# tdt_rereference.net
KiCad netlist of a schematic drawn in EAGLE
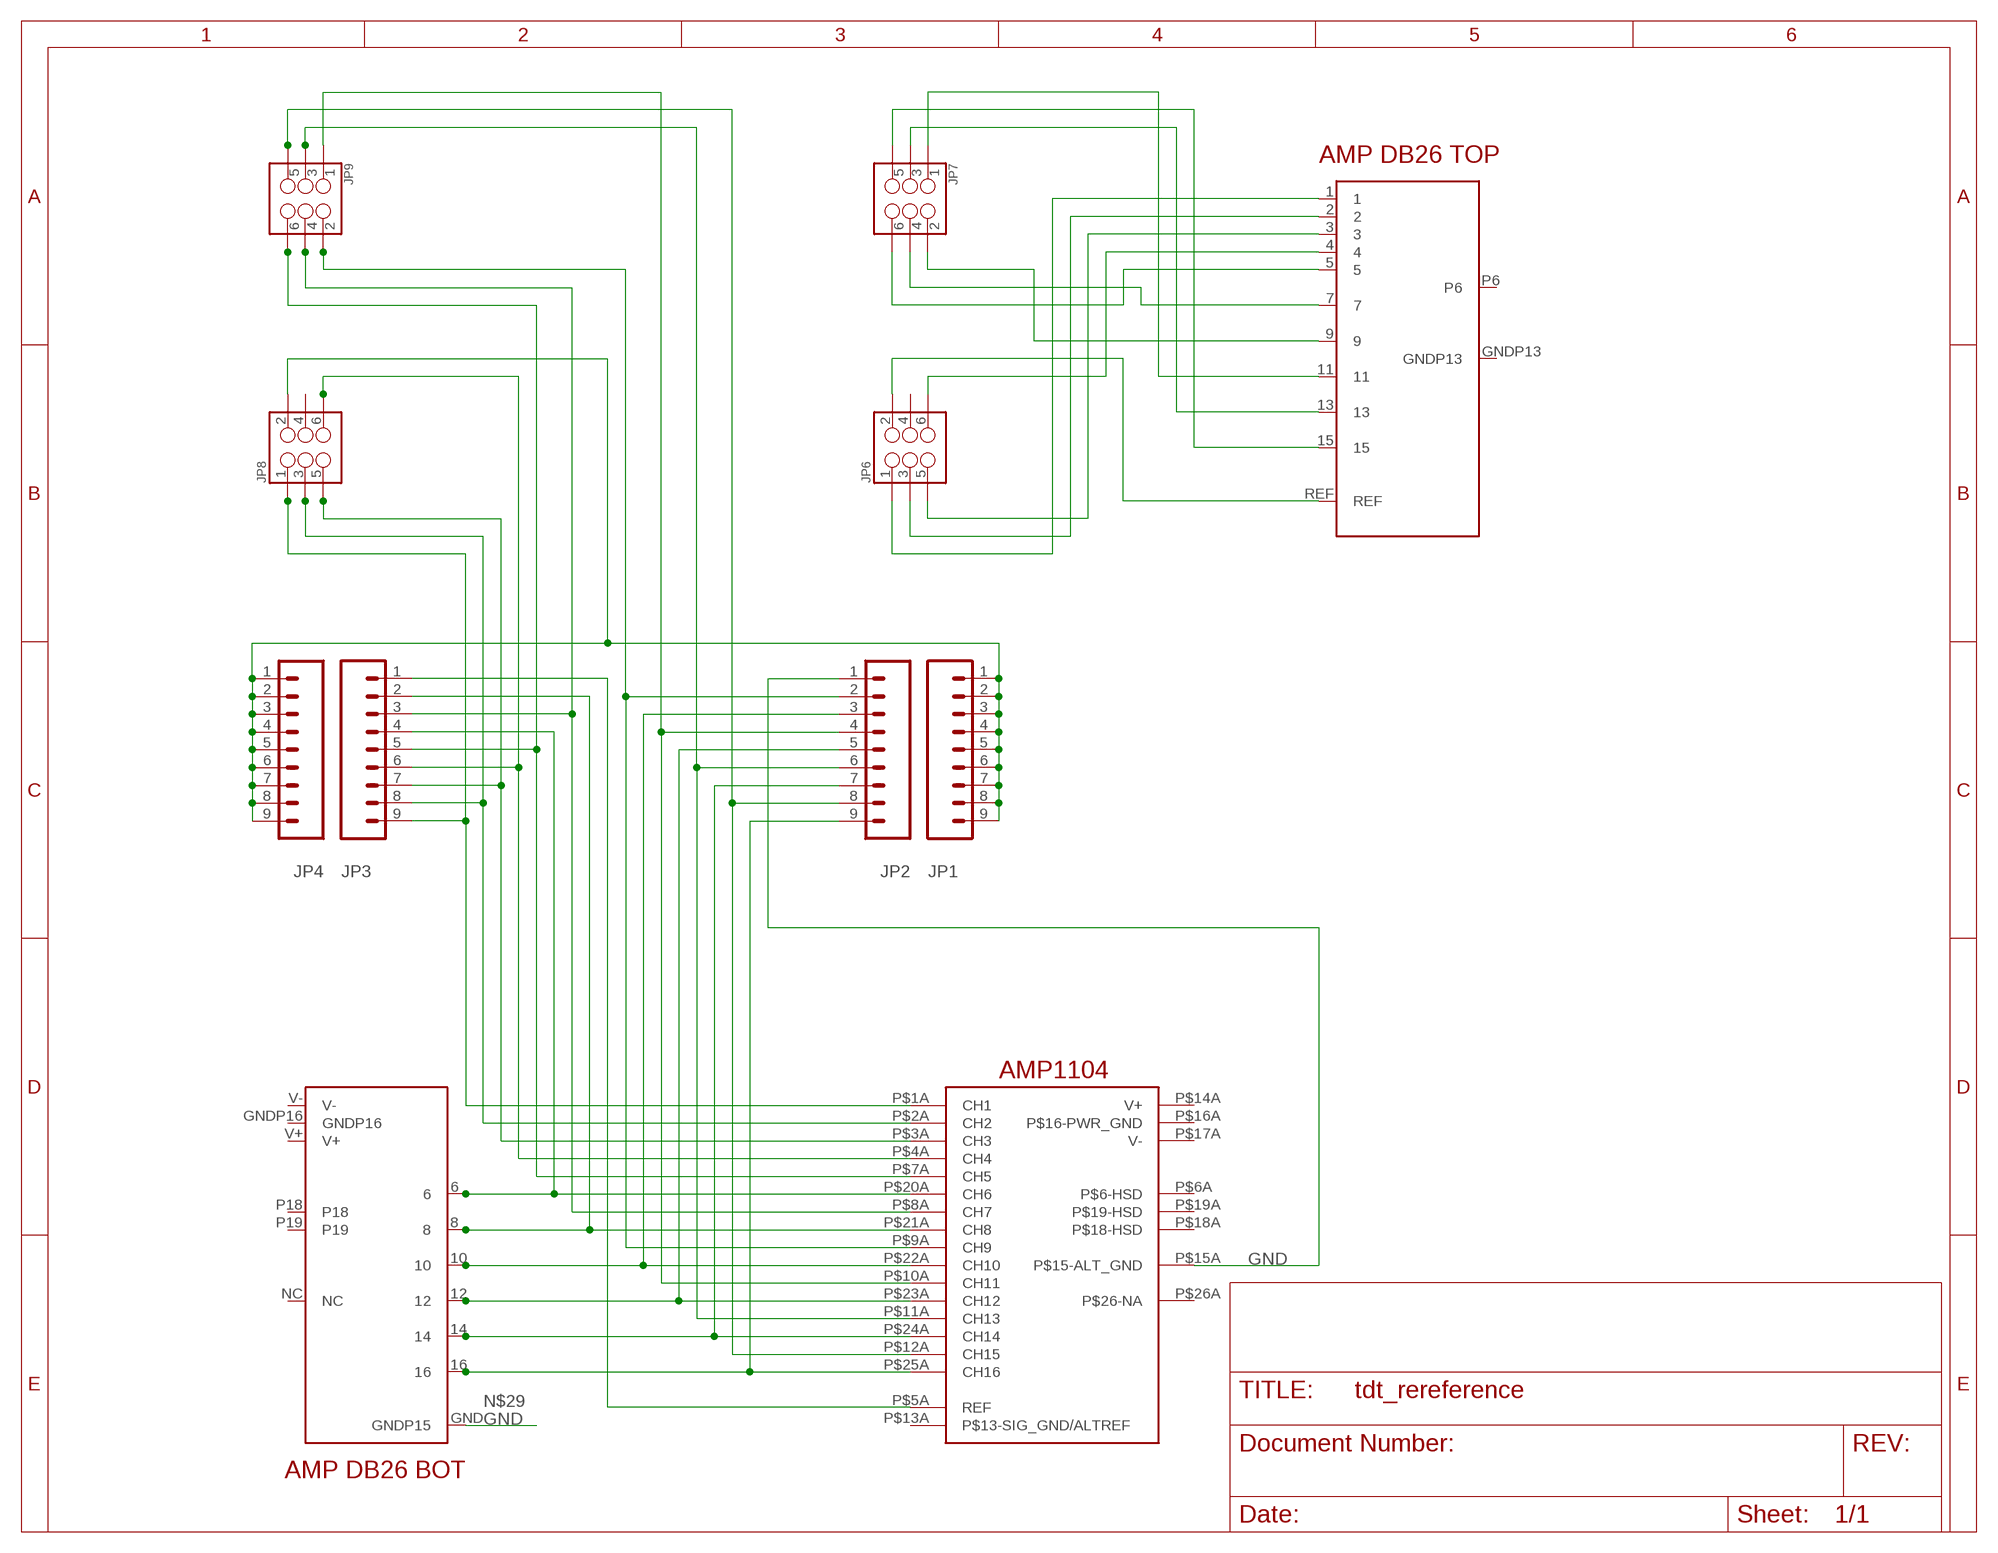
[diagram p0: schematic, sheet 1]

(export (version "E")
  (design (tool "Eeschema 10.0.6"))
  (components
    (comp (ref "JP1")
      (value "M09")
      (footprint "eagle-import:1X09")
      (libsource (lib "eagle-import") (part "M09"))
    )
    (comp (ref "JP2")
      (value "M09")
      (footprint "eagle-import:1X09")
      (libsource (lib "eagle-import") (part "M09"))
    )
    (comp (ref "JP3")
      (value "M09")
      (footprint "eagle-import:1X09")
      (libsource (lib "eagle-import") (part "M09"))
    )
    (comp (ref "JP4")
      (value "M09")
      (footprint "eagle-import:1X09")
      (libsource (lib "eagle-import") (part "M09"))
    )
    (comp (ref "JP6")
      (value "M03X22X3_SILK_MALE_PTH")
      (footprint "eagle-import:2X3")
      (libsource (lib "eagle-import") (part "M03X22X3_SILK_MALE_PTH"))
    )
    (comp (ref "JP7")
      (value "M03X22X3_SILK_MALE_PTH")
      (footprint "eagle-import:2X3")
      (libsource (lib "eagle-import") (part "M03X22X3_SILK_MALE_PTH"))
    )
    (comp (ref "JP8")
      (value "M03X22X3_SILK_MALE_PTH")
      (footprint "eagle-import:2X3")
      (libsource (lib "eagle-import") (part "M03X22X3_SILK_MALE_PTH"))
    )
    (comp (ref "JP9")
      (value "M03X22X3_SILK_MALE_PTH")
      (footprint "eagle-import:2X3")
      (libsource (lib "eagle-import") (part "M03X22X3_SILK_MALE_PTH"))
    )
    (comp (ref "U$1")
      (value "DB26-MALE-BOT")
      (footprint "eagle-import:DB26-MALE-BOT")
      (libsource (lib "eagle-import") (part "DB26-MALE-BOT"))
    )
    (comp (ref "U$2")
      (value "DB26-MALE-TOP")
      (footprint "eagle-import:DB26-MALE-TOP")
      (libsource (lib "eagle-import") (part "DB26-MALE-TOP"))
    )
    (comp (ref "U$3")
      (value "AMP1104")
      (footprint "eagle-import:AMP1104")
      (libsource (lib "eagle-import") (part "AMP1104"))
    )
  )
  (nets
    (net (code "1") (name "/GND") (class "Default")
      (node (ref "JP2") (pin "1") (pinfunction "1_1") (pintype "passive"))
      (node (ref "U$1") (pin "GND") (pinfunction "GNDP15_GND") (pintype "bidirectional"))
      (node (ref "U$3") (pin "P$15A") (pinfunction "P$15-ALT_GND_P$15A") (pintype "bidirectional"))
    )
    (net (code "2") (name "/N$29") (class "Default")
      (node (ref "JP3") (pin "1") (pinfunction "1_1") (pintype "passive"))
      (node (ref "U$3") (pin "P$5A") (pinfunction "REF_P$5A") (pintype "bidirectional"))
    )
    (net (code "3") (name "Net-(JP1-Pad1)") (class "Default")
      (node (ref "JP1") (pin "1") (pinfunction "1_1") (pintype "passive"))
      (node (ref "JP1") (pin "2") (pinfunction "2_2") (pintype "passive"))
      (node (ref "JP1") (pin "3") (pinfunction "3_3") (pintype "passive"))
      (node (ref "JP1") (pin "4") (pinfunction "4_4") (pintype "passive"))
      (node (ref "JP1") (pin "5") (pinfunction "5_5") (pintype "passive"))
      (node (ref "JP1") (pin "6") (pinfunction "6_6") (pintype "passive"))
      (node (ref "JP1") (pin "7") (pinfunction "7_7") (pintype "passive"))
      (node (ref "JP1") (pin "8") (pinfunction "8_8") (pintype "passive"))
      (node (ref "JP1") (pin "9") (pinfunction "9_9") (pintype "passive"))
      (node (ref "JP4") (pin "1") (pinfunction "1_1") (pintype "passive"))
      (node (ref "JP4") (pin "2") (pinfunction "2_2") (pintype "passive"))
      (node (ref "JP4") (pin "3") (pinfunction "3_3") (pintype "passive"))
      (node (ref "JP4") (pin "4") (pinfunction "4_4") (pintype "passive"))
      (node (ref "JP4") (pin "5") (pinfunction "5_5") (pintype "passive"))
      (node (ref "JP4") (pin "6") (pinfunction "6_6") (pintype "passive"))
      (node (ref "JP4") (pin "7") (pinfunction "7_7") (pintype "passive"))
      (node (ref "JP4") (pin "8") (pinfunction "8_8") (pintype "passive"))
      (node (ref "JP4") (pin "9") (pinfunction "9_9") (pintype "passive"))
      (node (ref "JP8") (pin "2") (pinfunction "2_2") (pintype "bidirectional"))
    )
    (net (code "4") (name "Net-(JP6-Pad1)") (class "Default")
      (node (ref "JP6") (pin "1") (pinfunction "1_1") (pintype "bidirectional"))
      (node (ref "U$2") (pin "1") (pinfunction "1_1") (pintype "bidirectional"))
    )
    (net (code "5") (name "Net-(JP6-Pad2)") (class "Default")
      (node (ref "JP6") (pin "2") (pinfunction "2_2") (pintype "bidirectional"))
      (node (ref "U$2") (pin "REF") (pinfunction "REF_REF") (pintype "bidirectional"))
    )
    (net (code "6") (name "Net-(JP6-Pad3)") (class "Default")
      (node (ref "JP6") (pin "3") (pinfunction "3_3") (pintype "bidirectional"))
      (node (ref "U$2") (pin "2") (pinfunction "2_2") (pintype "bidirectional"))
    )
    (net (code "7") (name "Net-(JP6-Pad5)") (class "Default")
      (node (ref "JP6") (pin "5") (pinfunction "5_5") (pintype "bidirectional"))
      (node (ref "U$2") (pin "3") (pinfunction "3_3") (pintype "bidirectional"))
    )
    (net (code "8") (name "Net-(JP6-Pad6)") (class "Default")
      (node (ref "JP6") (pin "6") (pinfunction "6_6") (pintype "bidirectional"))
      (node (ref "U$2") (pin "4") (pinfunction "4_4") (pintype "bidirectional"))
    )
    (net (code "9") (name "Net-(JP7-Pad1)") (class "Default")
      (node (ref "JP7") (pin "1") (pinfunction "1_1") (pintype "bidirectional"))
      (node (ref "U$2") (pin "11") (pinfunction "11_11") (pintype "bidirectional"))
    )
    (net (code "10") (name "Net-(JP7-Pad2)") (class "Default")
      (node (ref "JP7") (pin "2") (pinfunction "2_2") (pintype "bidirectional"))
      (node (ref "U$2") (pin "9") (pinfunction "9_9") (pintype "bidirectional"))
    )
    (net (code "11") (name "Net-(JP7-Pad3)") (class "Default")
      (node (ref "JP7") (pin "3") (pinfunction "3_3") (pintype "bidirectional"))
      (node (ref "U$2") (pin "13") (pinfunction "13_13") (pintype "bidirectional"))
    )
    (net (code "12") (name "Net-(JP7-Pad4)") (class "Default")
      (node (ref "JP7") (pin "4") (pinfunction "4_4") (pintype "bidirectional"))
      (node (ref "U$2") (pin "7") (pinfunction "7_7") (pintype "bidirectional"))
    )
    (net (code "13") (name "Net-(JP7-Pad5)") (class "Default")
      (node (ref "JP7") (pin "5") (pinfunction "5_5") (pintype "bidirectional"))
      (node (ref "U$2") (pin "15") (pinfunction "15_15") (pintype "bidirectional"))
    )
    (net (code "14") (name "Net-(JP7-Pad6)") (class "Default")
      (node (ref "JP7") (pin "6") (pinfunction "6_6") (pintype "bidirectional"))
      (node (ref "U$2") (pin "5") (pinfunction "5_5") (pintype "bidirectional"))
    )
    (net (code "15") (name "Net-(U$3-CH1)") (class "Default")
      (node (ref "JP3") (pin "9") (pinfunction "9_9") (pintype "passive"))
      (node (ref "JP8") (pin "1") (pinfunction "1_1") (pintype "bidirectional"))
      (node (ref "U$3") (pin "P$1A") (pinfunction "CH1_P$1A") (pintype "bidirectional"))
    )
    (net (code "16") (name "Net-(U$3-CH2)") (class "Default")
      (node (ref "JP3") (pin "8") (pinfunction "8_8") (pintype "passive"))
      (node (ref "JP8") (pin "3") (pinfunction "3_3") (pintype "bidirectional"))
      (node (ref "U$3") (pin "P$2A") (pinfunction "CH2_P$2A") (pintype "bidirectional"))
    )
    (net (code "17") (name "Net-(U$3-CH3)") (class "Default")
      (node (ref "JP3") (pin "7") (pinfunction "7_7") (pintype "passive"))
      (node (ref "JP8") (pin "5") (pinfunction "5_5") (pintype "bidirectional"))
      (node (ref "U$3") (pin "P$3A") (pinfunction "CH3_P$3A") (pintype "bidirectional"))
    )
    (net (code "18") (name "Net-(U$3-CH4)") (class "Default")
      (node (ref "JP3") (pin "6") (pinfunction "6_6") (pintype "passive"))
      (node (ref "JP8") (pin "6") (pinfunction "6_6") (pintype "bidirectional"))
      (node (ref "U$3") (pin "P$4A") (pinfunction "CH4_P$4A") (pintype "bidirectional"))
    )
    (net (code "19") (name "Net-(U$3-CH5)") (class "Default")
      (node (ref "JP3") (pin "5") (pinfunction "5_5") (pintype "passive"))
      (node (ref "JP9") (pin "6") (pinfunction "6_6") (pintype "bidirectional"))
      (node (ref "U$3") (pin "P$7A") (pinfunction "CH5_P$7A") (pintype "bidirectional"))
    )
    (net (code "20") (name "Net-(U$3-CH6)") (class "Default")
      (node (ref "JP3") (pin "4") (pinfunction "4_4") (pintype "passive"))
      (node (ref "U$1") (pin "6") (pinfunction "6_6") (pintype "bidirectional"))
      (node (ref "U$3") (pin "P$20A") (pinfunction "CH6_P$20A") (pintype "bidirectional"))
    )
    (net (code "21") (name "Net-(U$3-CH7)") (class "Default")
      (node (ref "JP3") (pin "3") (pinfunction "3_3") (pintype "passive"))
      (node (ref "JP9") (pin "4") (pinfunction "4_4") (pintype "bidirectional"))
      (node (ref "U$3") (pin "P$8A") (pinfunction "CH7_P$8A") (pintype "bidirectional"))
    )
    (net (code "22") (name "Net-(U$3-CH8)") (class "Default")
      (node (ref "JP3") (pin "2") (pinfunction "2_2") (pintype "passive"))
      (node (ref "U$1") (pin "8") (pinfunction "8_8") (pintype "bidirectional"))
      (node (ref "U$3") (pin "P$21A") (pinfunction "CH8_P$21A") (pintype "bidirectional"))
    )
    (net (code "23") (name "Net-(U$3-CH9)") (class "Default")
      (node (ref "JP2") (pin "2") (pinfunction "2_2") (pintype "passive"))
      (node (ref "JP9") (pin "2") (pinfunction "2_2") (pintype "bidirectional"))
      (node (ref "U$3") (pin "P$9A") (pinfunction "CH9_P$9A") (pintype "bidirectional"))
    )
    (net (code "24") (name "Net-(U$3-CH10)") (class "Default")
      (node (ref "JP2") (pin "3") (pinfunction "3_3") (pintype "passive"))
      (node (ref "U$1") (pin "10") (pinfunction "10_10") (pintype "bidirectional"))
      (node (ref "U$3") (pin "P$22A") (pinfunction "CH10_P$22A") (pintype "bidirectional"))
    )
    (net (code "25") (name "Net-(U$3-CH11)") (class "Default")
      (node (ref "JP2") (pin "4") (pinfunction "4_4") (pintype "passive"))
      (node (ref "JP9") (pin "1") (pinfunction "1_1") (pintype "bidirectional"))
      (node (ref "U$3") (pin "P$10A") (pinfunction "CH11_P$10A") (pintype "bidirectional"))
    )
    (net (code "26") (name "Net-(U$3-CH12)") (class "Default")
      (node (ref "JP2") (pin "5") (pinfunction "5_5") (pintype "passive"))
      (node (ref "U$1") (pin "12") (pinfunction "12_12") (pintype "bidirectional"))
      (node (ref "U$3") (pin "P$23A") (pinfunction "CH12_P$23A") (pintype "bidirectional"))
    )
    (net (code "27") (name "Net-(U$3-CH13)") (class "Default")
      (node (ref "JP2") (pin "6") (pinfunction "6_6") (pintype "passive"))
      (node (ref "JP9") (pin "3") (pinfunction "3_3") (pintype "bidirectional"))
      (node (ref "U$3") (pin "P$11A") (pinfunction "CH13_P$11A") (pintype "bidirectional"))
    )
    (net (code "28") (name "Net-(U$3-CH14)") (class "Default")
      (node (ref "JP2") (pin "7") (pinfunction "7_7") (pintype "passive"))
      (node (ref "U$1") (pin "14") (pinfunction "14_14") (pintype "bidirectional"))
      (node (ref "U$3") (pin "P$24A") (pinfunction "CH14_P$24A") (pintype "bidirectional"))
    )
    (net (code "29") (name "Net-(U$3-CH15)") (class "Default")
      (node (ref "JP2") (pin "8") (pinfunction "8_8") (pintype "passive"))
      (node (ref "JP9") (pin "5") (pinfunction "5_5") (pintype "bidirectional"))
      (node (ref "U$3") (pin "P$12A") (pinfunction "CH15_P$12A") (pintype "bidirectional"))
    )
    (net (code "30") (name "Net-(U$3-CH16)") (class "Default")
      (node (ref "JP2") (pin "9") (pinfunction "9_9") (pintype "passive"))
      (node (ref "U$1") (pin "16") (pinfunction "16_16") (pintype "bidirectional"))
      (node (ref "U$3") (pin "P$25A") (pinfunction "CH16_P$25A") (pintype "bidirectional"))
    )
    (net (code "31") (name "unconnected-(JP6-Pad4)") (class "Default")
      (node (ref "JP6") (pin "4") (pinfunction "4_4") (pintype "bidirectional"))
    )
    (net (code "32") (name "unconnected-(JP8-Pad4)") (class "Default")
      (node (ref "JP8") (pin "4") (pinfunction "4_4") (pintype "bidirectional"))
    )
    (net (code "33") (name "unconnected-(U$1-PadGNDP16)") (class "Default")
      (node (ref "U$1") (pin "GNDP16") (pinfunction "GNDP16_GNDP16") (pintype "bidirectional"))
    )
    (net (code "34") (name "unconnected-(U$1-PadNC)") (class "Default")
      (node (ref "U$1") (pin "NC") (pinfunction "NC_NC") (pintype "bidirectional"))
    )
    (net (code "35") (name "unconnected-(U$1-PadP18)") (class "Default")
      (node (ref "U$1") (pin "P18") (pinfunction "P18_P18") (pintype "bidirectional"))
    )
    (net (code "36") (name "unconnected-(U$1-PadP19)") (class "Default")
      (node (ref "U$1") (pin "P19") (pinfunction "P19_P19") (pintype "bidirectional"))
    )
    (net (code "37") (name "unconnected-(U$1-PadV+)") (class "Default")
      (node (ref "U$1") (pin "V+") (pinfunction "V+_V+") (pintype "bidirectional"))
    )
    (net (code "38") (name "unconnected-(U$1-PadV-)") (class "Default")
      (node (ref "U$1") (pin "V-") (pinfunction "V-_V-") (pintype "bidirectional"))
    )
    (net (code "39") (name "unconnected-(U$2-PadGNDP13)") (class "Default")
      (node (ref "U$2") (pin "GNDP13") (pinfunction "GNDP13_GNDP13") (pintype "bidirectional"))
    )
    (net (code "40") (name "unconnected-(U$2-PadP6)") (class "Default")
      (node (ref "U$2") (pin "P6") (pinfunction "P6_P6") (pintype "bidirectional"))
    )
    (net (code "41") (name "unconnected-(U$3-P$6-HSD-PadP$6A)") (class "Default")
      (node (ref "U$3") (pin "P$6A") (pinfunction "P$6-HSD_P$6A") (pintype "bidirectional"))
    )
    (net (code "42") (name "unconnected-(U$3-P$13-SIG_GND{slash}ALTREF-PadP$13A)") (class "Default")
      (node (ref "U$3") (pin "P$13A") (pinfunction "P$13-SIG_GND/ALTREF_P$13A") (pintype "bidirectional"))
    )
    (net (code "43") (name "unconnected-(U$3-P$16-PWR_GND-PadP$16A)") (class "Default")
      (node (ref "U$3") (pin "P$16A") (pinfunction "P$16-PWR_GND_P$16A") (pintype "bidirectional"))
    )
    (net (code "44") (name "unconnected-(U$3-P$18-HSD-PadP$18A)") (class "Default")
      (node (ref "U$3") (pin "P$18A") (pinfunction "P$18-HSD_P$18A") (pintype "bidirectional"))
    )
    (net (code "45") (name "unconnected-(U$3-P$19-HSD-PadP$19A)") (class "Default")
      (node (ref "U$3") (pin "P$19A") (pinfunction "P$19-HSD_P$19A") (pintype "bidirectional"))
    )
    (net (code "46") (name "unconnected-(U$3-P$26-NA-PadP$26A)") (class "Default")
      (node (ref "U$3") (pin "P$26A") (pinfunction "P$26-NA_P$26A") (pintype "bidirectional"))
    )
    (net (code "47") (name "unconnected-(U$3-V+-PadP$14A)") (class "Default")
      (node (ref "U$3") (pin "P$14A") (pinfunction "V+_P$14A") (pintype "bidirectional"))
    )
    (net (code "48") (name "unconnected-(U$3-V--PadP$17A)") (class "Default")
      (node (ref "U$3") (pin "P$17A") (pinfunction "V-_P$17A") (pintype "bidirectional"))
    )
  )
)
